# LDO_LD.net
KiCad netlist of a schematic drawn in Altium Designer
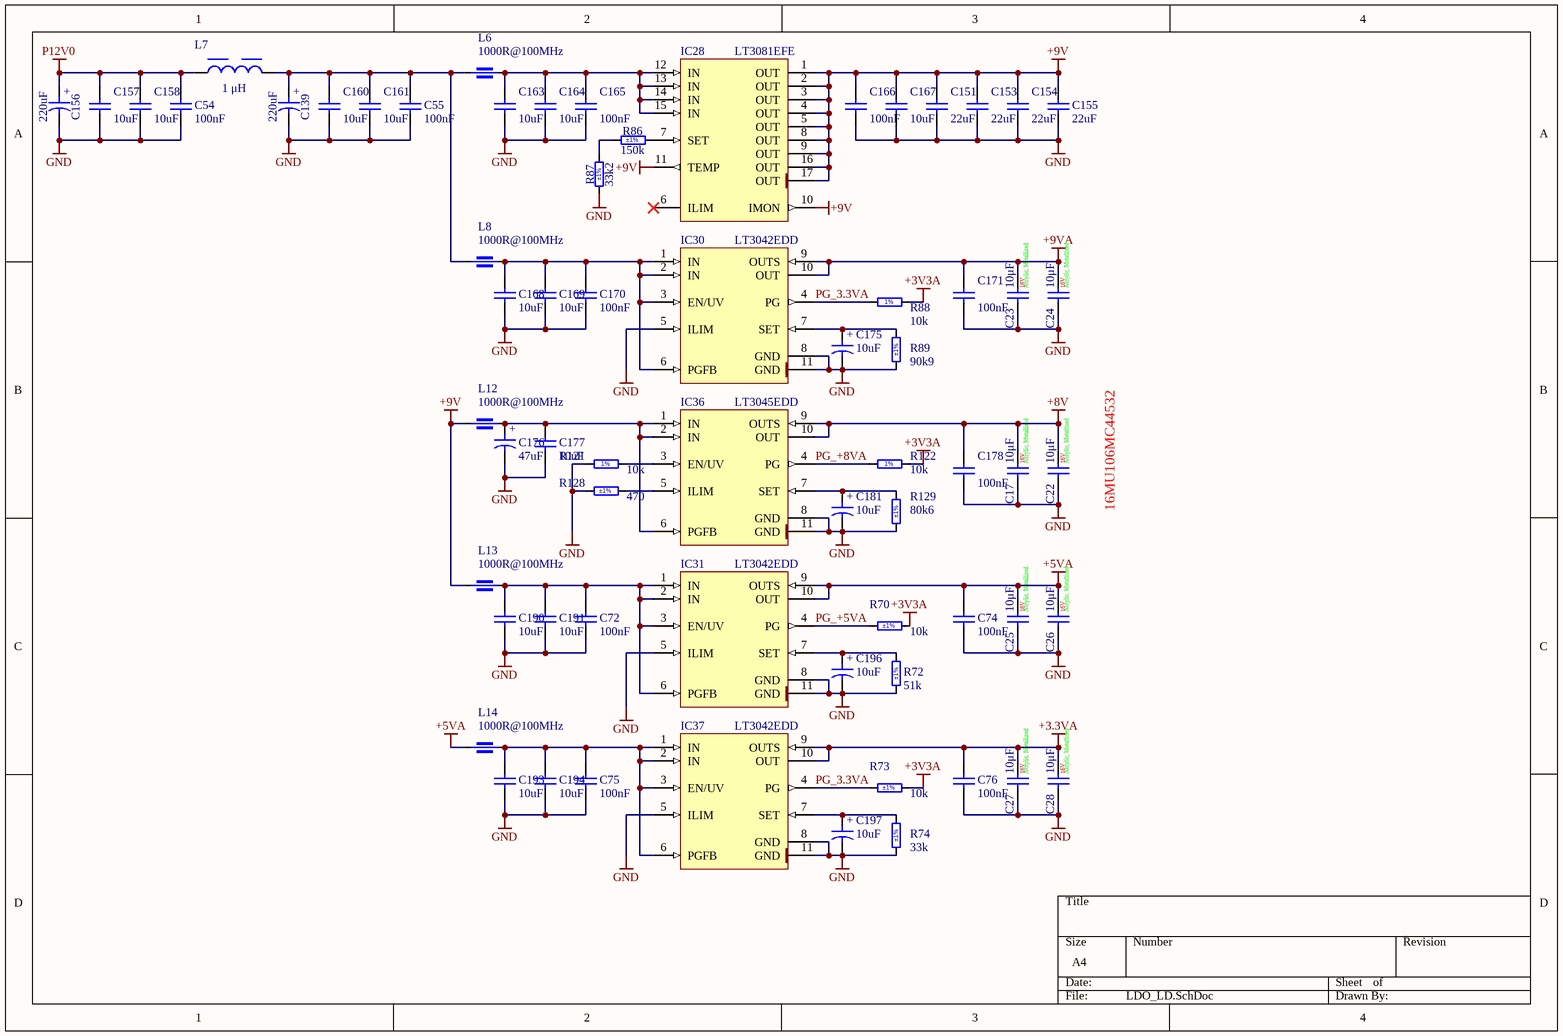
[diagram p0: LDO_LD.SchDoc]

(export (version "E")
  (design (tool "Eeschema 10.0.6"))
  (components
    (comp (ref "C17")
      (value "16MU106MC44532")
      (footprint "16MU106MC44532")
      (description "10 µF Film Capacitor 16V Acrylic, Metallized 1812 (4532 Metric)")
      (fields
        (field (name "DIELECTRIKTYPE") "Acrylic, Metallized")
        (field (name "VALUE1") "10μF")
        (field (name "VALUE2") "16V")
      )
      (libsource (lib "Component Library 3.2") (part "10uF/16V/1812/MET"))
    )
    (comp (ref "C22")
      (value "16MU106MC44532")
      (footprint "16MU106MC44532")
      (description "10 µF Film Capacitor 16V Acrylic, Metallized 1812 (4532 Metric)")
      (fields
        (field (name "DIELECTRIKTYPE") "Acrylic, Metallized")
        (field (name "VALUE1") "10μF")
        (field (name "VALUE2") "16V")
      )
      (libsource (lib "Component Library 3.2") (part "10uF/16V/1812/MET"))
    )
    (comp (ref "C23")
      (value "16MU106MC44532")
      (footprint "16MU106MC44532")
      (description "10 µF Film Capacitor 16V Acrylic, Metallized 1812 (4532 Metric)")
      (fields
        (field (name "DIELECTRIKTYPE") "Acrylic, Metallized")
        (field (name "VALUE1") "10μF")
        (field (name "VALUE2") "16V")
      )
      (libsource (lib "Component Library 3.2") (part "10uF/16V/1812/MET"))
    )
    (comp (ref "C24")
      (value "16MU106MC44532")
      (footprint "16MU106MC44532")
      (description "10 µF Film Capacitor 16V Acrylic, Metallized 1812 (4532 Metric)")
      (fields
        (field (name "DIELECTRIKTYPE") "Acrylic, Metallized")
        (field (name "VALUE1") "10μF")
        (field (name "VALUE2") "16V")
      )
      (libsource (lib "Component Library 3.2") (part "10uF/16V/1812/MET"))
    )
    (comp (ref "C25")
      (value "16MU106MC44532")
      (footprint "16MU106MC44532")
      (description "10 µF Film Capacitor 16V Acrylic, Metallized 1812 (4532 Metric)")
      (fields
        (field (name "DIELECTRIKTYPE") "Acrylic, Metallized")
        (field (name "VALUE1") "10μF")
        (field (name "VALUE2") "16V")
      )
      (libsource (lib "Component Library 3.2") (part "10uF/16V/1812/MET"))
    )
    (comp (ref "C26")
      (value "16MU106MC44532")
      (footprint "16MU106MC44532")
      (description "10 µF Film Capacitor 16V Acrylic, Metallized 1812 (4532 Metric)")
      (fields
        (field (name "DIELECTRIKTYPE") "Acrylic, Metallized")
        (field (name "VALUE1") "10μF")
        (field (name "VALUE2") "16V")
      )
      (libsource (lib "Component Library 3.2") (part "10uF/16V/1812/MET"))
    )
    (comp (ref "C27")
      (value "16MU106MC44532")
      (footprint "16MU106MC44532")
      (description "10 µF Film Capacitor 16V Acrylic, Metallized 1812 (4532 Metric)")
      (fields
        (field (name "DIELECTRIKTYPE") "Acrylic, Metallized")
        (field (name "VALUE1") "10μF")
        (field (name "VALUE2") "16V")
      )
      (libsource (lib "Component Library 3.2") (part "10uF/16V/1812/MET"))
    )
    (comp (ref "C28")
      (value "16MU106MC44532")
      (footprint "16MU106MC44532")
      (description "10 µF Film Capacitor 16V Acrylic, Metallized 1812 (4532 Metric)")
      (fields
        (field (name "DIELECTRIKTYPE") "Acrylic, Metallized")
        (field (name "VALUE1") "10μF")
        (field (name "VALUE2") "16V")
      )
      (libsource (lib "Component Library 3.2") (part "10uF/16V/1812/MET"))
    )
    (comp (ref "C54")
      (value "100nF")
      (footprint "CAPC1005X55N")
      (description "Non-polarised capacitor")
      (fields
        (field (name "PART NUMBER") "CC0402_100NF_16V_10%_X5R")
        (field (name "VOLTAGE") "16V")
        (field (name "AUTHOR") "CERN DEM JLC")
      )
      (libsource (lib "Capacitors") (part "Capacitor - non polarized"))
    )
    (comp (ref "C55")
      (value "100nF")
      (footprint "CAPC1005X55N")
      (description "Non-polarised capacitor")
      (fields
        (field (name "PART NUMBER") "CC0402_100NF_16V_10%_X5R")
        (field (name "VOLTAGE") "16V")
        (field (name "AUTHOR") "CERN DEM JLC")
      )
      (libsource (lib "Capacitors") (part "Capacitor - non polarized"))
    )
    (comp (ref "C72")
      (value "100nF")
      (footprint "CAPC1005X55N")
      (description "Non-polarised capacitor")
      (fields
        (field (name "PART NUMBER") "CC0402_100NF_16V_10%_X5R")
        (field (name "VOLTAGE") "16V")
        (field (name "AUTHOR") "CERN DEM JLC")
      )
      (libsource (lib "Capacitors") (part "Capacitor - non polarized"))
    )
    (comp (ref "C74")
      (value "100nF")
      (footprint "CAPC1005X55N")
      (description "Non-polarised capacitor")
      (fields
        (field (name "PART NUMBER") "CC0402_100NF_16V_10%_X5R")
        (field (name "VOLTAGE") "16V")
        (field (name "AUTHOR") "CERN DEM JLC")
      )
      (libsource (lib "Capacitors") (part "Capacitor - non polarized"))
    )
    (comp (ref "C75")
      (value "100nF")
      (footprint "CAPC1005X55N")
      (description "Non-polarised capacitor")
      (fields
        (field (name "PART NUMBER") "CC0402_100NF_16V_10%_X5R")
        (field (name "VOLTAGE") "16V")
        (field (name "AUTHOR") "CERN DEM JLC")
      )
      (libsource (lib "Capacitors") (part "Capacitor - non polarized"))
    )
    (comp (ref "C76")
      (value "100nF")
      (footprint "CAPC1005X55N")
      (description "Non-polarised capacitor")
      (fields
        (field (name "PART NUMBER") "CC0402_100NF_16V_10%_X5R")
        (field (name "VOLTAGE") "16V")
        (field (name "AUTHOR") "CERN DEM JLC")
      )
      (libsource (lib "Capacitors") (part "Capacitor - non polarized"))
    )
    (comp (ref "C139")
      (value "220uF")
      (footprint "CAPMP7343X430N")
      (description "Polarised capacitor")
      (fields
        (field (name "PART NUMBER") "CTE7343-43_220UF_16V_10%")
        (field (name "VOLTAGE") "16V")
        (field (name "AUTHOR") "CERN DEM JLC")
      )
      (libsource (lib "Capacitors") (part "Capacitor - polarized"))
    )
    (comp (ref "C151")
      (value "22uF")
      (footprint "CAPC3216X180N")
      (description "Non-polarised capacitor")
      (fields
        (field (name "PART NUMBER") "CC1206_22UF_10V_10%_X7R")
        (field (name "VOLTAGE") "10V")
        (field (name "AUTHOR") "CERN DEM JLC")
      )
      (libsource (lib "Capacitors") (part "Capacitor - non polarized"))
    )
    (comp (ref "C153")
      (value "22uF")
      (footprint "CAPC3216X180N")
      (description "Non-polarised capacitor")
      (fields
        (field (name "PART NUMBER") "CC1206_22UF_10V_10%_X7R")
        (field (name "VOLTAGE") "10V")
        (field (name "AUTHOR") "CERN DEM JLC")
      )
      (libsource (lib "Capacitors") (part "Capacitor - non polarized"))
    )
    (comp (ref "C154")
      (value "22uF")
      (footprint "CAPC3216X180N")
      (description "Non-polarised capacitor")
      (fields
        (field (name "PART NUMBER") "CC1206_22UF_10V_10%_X7R")
        (field (name "VOLTAGE") "10V")
        (field (name "AUTHOR") "CERN DEM JLC")
      )
      (libsource (lib "Capacitors") (part "Capacitor - non polarized"))
    )
    (comp (ref "C155")
      (value "22uF")
      (footprint "CAPC3216X180N")
      (description "Non-polarised capacitor")
      (fields
        (field (name "PART NUMBER") "CC1206_22UF_10V_10%_X7R")
        (field (name "VOLTAGE") "10V")
        (field (name "AUTHOR") "CERN DEM JLC")
      )
      (libsource (lib "Capacitors") (part "Capacitor - non polarized"))
    )
    (comp (ref "C156")
      (value "220uF")
      (footprint "CAPMP7343X430N")
      (description "Polarised capacitor")
      (fields
        (field (name "PART NUMBER") "CTE7343-43_220UF_16V_10%")
        (field (name "VOLTAGE") "16V")
        (field (name "AUTHOR") "CERN DEM JLC")
      )
      (libsource (lib "Capacitors") (part "Capacitor - polarized"))
    )
    (comp (ref "C157")
      (value "10uF")
      (footprint "CAPC2012X145N")
      (description "Non-polarised capacitor")
      (fields
        (field (name "PART NUMBER") "CC0805_10UF_25V_10%_X7R")
        (field (name "VOLTAGE") "25V")
        (field (name "AUTHOR") "CERN DEM HF")
      )
      (libsource (lib "Capacitors") (part "Capacitor - non polarized"))
    )
    (comp (ref "C158")
      (value "10uF")
      (footprint "CAPC2012X145N")
      (description "Non-polarised capacitor")
      (fields
        (field (name "PART NUMBER") "CC0805_10UF_25V_10%_X7R")
        (field (name "VOLTAGE") "25V")
        (field (name "AUTHOR") "CERN DEM HF")
      )
      (libsource (lib "Capacitors") (part "Capacitor - non polarized"))
    )
    (comp (ref "C160")
      (value "10uF")
      (footprint "CAPC2012X145N")
      (description "Non-polarised capacitor")
      (fields
        (field (name "PART NUMBER") "CC0805_10UF_25V_10%_X7R")
        (field (name "VOLTAGE") "25V")
        (field (name "AUTHOR") "CERN DEM HF")
      )
      (libsource (lib "Capacitors") (part "Capacitor - non polarized"))
    )
    (comp (ref "C161")
      (value "10uF")
      (footprint "CAPC2012X145N")
      (description "Non-polarised capacitor")
      (fields
        (field (name "PART NUMBER") "CC0805_10UF_25V_10%_X7R")
        (field (name "VOLTAGE") "25V")
        (field (name "AUTHOR") "CERN DEM HF")
      )
      (libsource (lib "Capacitors") (part "Capacitor - non polarized"))
    )
    (comp (ref "C163")
      (value "10uF")
      (footprint "CAPC2012X145N")
      (description "Non-polarised capacitor")
      (fields
        (field (name "PART NUMBER") "CC0805_10UF_25V_10%_X7R")
        (field (name "VOLTAGE") "25V")
        (field (name "AUTHOR") "CERN DEM HF")
      )
      (libsource (lib "Capacitors") (part "Capacitor - non polarized"))
    )
    (comp (ref "C164")
      (value "10uF")
      (footprint "CAPC2012X145N")
      (description "Non-polarised capacitor")
      (fields
        (field (name "PART NUMBER") "CC0805_10UF_25V_10%_X7R")
        (field (name "VOLTAGE") "25V")
        (field (name "AUTHOR") "CERN DEM HF")
      )
      (libsource (lib "Capacitors") (part "Capacitor - non polarized"))
    )
    (comp (ref "C165")
      (value "100nF")
      (footprint "CAPC1005X55N")
      (description "Non-polarised capacitor")
      (fields
        (field (name "PART NUMBER") "CC0402_100NF_16V_10%_X5R")
        (field (name "VOLTAGE") "16V")
        (field (name "AUTHOR") "CERN DEM JLC")
      )
      (libsource (lib "Capacitors") (part "Capacitor - non polarized"))
    )
    (comp (ref "C166")
      (value "100nF")
      (footprint "CAPC1005X55N")
      (description "Non-polarised capacitor")
      (fields
        (field (name "PART NUMBER") "CC0402_100NF_16V_10%_X5R")
        (field (name "VOLTAGE") "16V")
        (field (name "AUTHOR") "CERN DEM JLC")
      )
      (libsource (lib "Capacitors") (part "Capacitor - non polarized"))
    )
    (comp (ref "C167")
      (value "10uF")
      (footprint "CAPC2012X145N")
      (description "Non-polarised capacitor")
      (fields
        (field (name "PART NUMBER") "CC0805_10UF_25V_10%_X7R")
        (field (name "VOLTAGE") "25V")
        (field (name "AUTHOR") "CERN DEM HF")
      )
      (libsource (lib "Capacitors") (part "Capacitor - non polarized"))
    )
    (comp (ref "C168")
      (value "10uF")
      (footprint "CAPC2012X145N")
      (description "Non-polarised capacitor")
      (fields
        (field (name "PART NUMBER") "CC0805_10UF_25V_10%_X7R")
        (field (name "VOLTAGE") "25V")
        (field (name "AUTHOR") "CERN DEM HF")
      )
      (libsource (lib "Capacitors") (part "Capacitor - non polarized"))
    )
    (comp (ref "C169")
      (value "10uF")
      (footprint "CAPC2012X145N")
      (description "Non-polarised capacitor")
      (fields
        (field (name "PART NUMBER") "CC0805_10UF_25V_10%_X7R")
        (field (name "VOLTAGE") "25V")
        (field (name "AUTHOR") "CERN DEM HF")
      )
      (libsource (lib "Capacitors") (part "Capacitor - non polarized"))
    )
    (comp (ref "C170")
      (value "100nF")
      (footprint "CAPC1005X55N")
      (description "Non-polarised capacitor")
      (fields
        (field (name "PART NUMBER") "CC0402_100NF_16V_10%_X5R")
        (field (name "VOLTAGE") "16V")
        (field (name "AUTHOR") "CERN DEM JLC")
      )
      (libsource (lib "Capacitors") (part "Capacitor - non polarized"))
    )
    (comp (ref "C171")
      (value "100nF")
      (footprint "CAPC1005X55N")
      (description "Non-polarised capacitor")
      (fields
        (field (name "PART NUMBER") "CC0402_100NF_16V_10%_X5R")
        (field (name "VOLTAGE") "16V")
        (field (name "AUTHOR") "CERN DEM JLC")
      )
      (libsource (lib "Capacitors") (part "Capacitor - non polarized"))
    )
    (comp (ref "C175")
      (value "10uF")
      (footprint "CAPMP6032X280N")
      (description "Polarised capacitor")
      (fields
        (field (name "PART NUMBER") "CTE6032-28_10UF_25V_10%_LESR0500")
        (field (name "VOLTAGE") "25V")
        (field (name "AUTHOR") "CERN DEM JLC")
      )
      (libsource (lib "Capacitors") (part "Capacitor - polarized"))
    )
    (comp (ref "C176")
      (value "47uF")
      (footprint "CAPMP6032X280N")
      (description "Polarised capacitor")
      (fields
        (field (name "PART NUMBER") "CTE6032-28_47UF_16V_10%_LESR0350")
        (field (name "VOLTAGE") "16V")
        (field (name "AUTHOR") "CERN DEM JLC")
      )
      (libsource (lib "Capacitors") (part "Capacitor - polarized"))
    )
    (comp (ref "C177")
      (value "10uF")
      (footprint "CAPC2012X145N")
      (description "Non-polarised capacitor")
      (fields
        (field (name "PART NUMBER") "CC0805_10UF_25V_10%_X7R")
        (field (name "VOLTAGE") "25V")
        (field (name "AUTHOR") "CERN DEM HF")
      )
      (libsource (lib "Capacitors") (part "Capacitor - non polarized"))
    )
    (comp (ref "C178")
      (value "100nF")
      (footprint "CAPC1005X55N")
      (description "Non-polarised capacitor")
      (fields
        (field (name "PART NUMBER") "CC0402_100NF_16V_10%_X5R")
        (field (name "VOLTAGE") "16V")
        (field (name "AUTHOR") "CERN DEM JLC")
      )
      (libsource (lib "Capacitors") (part "Capacitor - non polarized"))
    )
    (comp (ref "C181")
      (value "10uF")
      (footprint "CAPMP6032X280N")
      (description "Polarised capacitor")
      (fields
        (field (name "PART NUMBER") "CTE6032-28_10UF_25V_10%_LESR0500")
        (field (name "VOLTAGE") "25V")
        (field (name "AUTHOR") "CERN DEM JLC")
      )
      (libsource (lib "Capacitors") (part "Capacitor - polarized"))
    )
    (comp (ref "C190")
      (value "10uF")
      (footprint "CAPC2012X145N")
      (description "Non-polarised capacitor")
      (fields
        (field (name "PART NUMBER") "CC0805_10UF_25V_10%_X7R")
        (field (name "VOLTAGE") "25V")
        (field (name "AUTHOR") "CERN DEM HF")
      )
      (libsource (lib "Capacitors") (part "Capacitor - non polarized"))
    )
    (comp (ref "C191")
      (value "10uF")
      (footprint "CAPC2012X145N")
      (description "Non-polarised capacitor")
      (fields
        (field (name "PART NUMBER") "CC0805_10UF_25V_10%_X7R")
        (field (name "VOLTAGE") "25V")
        (field (name "AUTHOR") "CERN DEM HF")
      )
      (libsource (lib "Capacitors") (part "Capacitor - non polarized"))
    )
    (comp (ref "C193")
      (value "10uF")
      (footprint "CAPC2012X145N")
      (description "Non-polarised capacitor")
      (fields
        (field (name "PART NUMBER") "CC0805_10UF_25V_10%_X7R")
        (field (name "VOLTAGE") "25V")
        (field (name "AUTHOR") "CERN DEM HF")
      )
      (libsource (lib "Capacitors") (part "Capacitor - non polarized"))
    )
    (comp (ref "C194")
      (value "10uF")
      (footprint "CAPC2012X145N")
      (description "Non-polarised capacitor")
      (fields
        (field (name "PART NUMBER") "CC0805_10UF_25V_10%_X7R")
        (field (name "VOLTAGE") "25V")
        (field (name "AUTHOR") "CERN DEM HF")
      )
      (libsource (lib "Capacitors") (part "Capacitor - non polarized"))
    )
    (comp (ref "C196")
      (value "10uF")
      (footprint "CAPMP6032X280N")
      (description "Polarised capacitor")
      (fields
        (field (name "PART NUMBER") "CTE6032-28_10UF_25V_10%_LESR0500")
        (field (name "VOLTAGE") "25V")
        (field (name "AUTHOR") "CERN DEM JLC")
      )
      (libsource (lib "Capacitors") (part "Capacitor - polarized"))
    )
    (comp (ref "C197")
      (value "10uF")
      (footprint "CAPMP6032X280N")
      (description "Polarised capacitor")
      (fields
        (field (name "PART NUMBER") "CTE6032-28_10UF_25V_10%_LESR0500")
        (field (name "VOLTAGE") "25V")
        (field (name "AUTHOR") "CERN DEM JLC")
      )
      (libsource (lib "Capacitors") (part "Capacitor - polarized"))
    )
    (comp (ref "IC28")
      (value "LT3081EFE")
      (footprint "SOP65P640X110-17N-R294X358")
      (description "1.2 To 36V, 1.5A Single Resistor Rugged Linear Regulator With Monitors")
      (fields
        (field (name "PART NUMBER") "LT3081EFE#PBF")
        (field (name "MANUFACTURER") "LINEAR TECHNOLOGY")
        (field (name "AUTHOR") "CERN DEM MR")
      )
      (libsource (lib "ICs And Semiconductors") (part "LT3081EFE"))
    )
    (comp (ref "IC30")
      (value "LT3042EDD")
      (footprint "SON50P300X300X80-11N-R175X248")
      (description "20V, 200mA, Ultralow Noise, Ultrahigh PSRR RF Linear Regulator")
      (fields (field (name "MANUFACTURER") "ANALOG DEVICES") (field (name "AUTHOR") "CERN DEM HF"))
      (libsource (lib "ICs And Semiconductors") (part "LT3042"))
    )
    (comp (ref "IC31")
      (value "LT3042EDD")
      (footprint "SON50P300X300X80-11N-R175X248")
      (description "20V, 200mA, Ultralow Noise, Ultrahigh PSRR RF Linear Regulator")
      (fields (field (name "MANUFACTURER") "ANALOG DEVICES") (field (name "AUTHOR") "CERN DEM HF"))
      (libsource (lib "ICs And Semiconductors") (part "LT3042"))
    )
    (comp (ref "IC36")
      (value "LT3045EDD")
      (footprint "SON50P300X300X80-11N-R175X248")
      (description "20V, 500mA, Ultralow Noise, Ultrahigh PSRR Linear Regulator")
      (fields
        (field (name "PART NUMBER") "LT3045EDD#PBF")
        (field (name "MANUFACTURER") "LINEAR TECHNOLOGY")
        (field (name "AUTHOR") "CERN DEM JLC")
      )
      (libsource (lib "ICs And Semiconductors") (part "LT3045EDD"))
    )
    (comp (ref "IC37")
      (value "LT3042EDD")
      (footprint "SON50P300X300X80-11N-R175X248")
      (description "20V, 200mA, Ultralow Noise, Ultrahigh PSRR RF Linear Regulator")
      (fields (field (name "MANUFACTURER") "ANALOG DEVICES") (field (name "AUTHOR") "CERN DEM HF"))
      (libsource (lib "ICs And Semiconductors") (part "LT3042"))
    )
    (comp (ref "L6")
      (value "1000R@100MHz")
      (footprint "INDC1608X95N")
      (fields
        (field (name "PART NUMBER") "IND0603_MURATA_BLM18KG102SN1")
        (field (name "POWER") "1A")
        (field (name "TOLERANCE") "±25%")
        (field (name "AUTHOR") "CERN DEM HF")
      )
      (libsource (lib "Inductors & Transformers") (part "Ferrite Bead"))
    )
    (comp (ref "L7")
      (value "1 μH")
      (footprint "WE-MAPI_2510")
      (description "WE-MAPI SMT Power Inductor, size 2510, 1 μH, 3.55 A, 63 mΩ")
      (fields
        (field (name "MANUFACTURER PART NUMBER") "74438323010")
        (field (name "MANUFACTURER") "Wurth Elektronik")
      )
      (libsource (lib "WE-MAPI (rev25a)") (part "74438323010"))
    )
    (comp (ref "L8")
      (value "1000R@100MHz")
      (footprint "INDC1608X95N")
      (fields
        (field (name "PART NUMBER") "IND0603_MURATA_BLM18KG102SN1")
        (field (name "POWER") "1A")
        (field (name "TOLERANCE") "±25%")
        (field (name "AUTHOR") "CERN DEM HF")
      )
      (libsource (lib "Inductors & Transformers") (part "Ferrite Bead"))
    )
    (comp (ref "L12")
      (value "1000R@100MHz")
      (footprint "INDC1608X95N")
      (fields
        (field (name "PART NUMBER") "IND0603_MURATA_BLM18KG102SN1")
        (field (name "POWER") "1A")
        (field (name "TOLERANCE") "±25%")
        (field (name "AUTHOR") "CERN DEM HF")
      )
      (libsource (lib "Inductors & Transformers") (part "Ferrite Bead"))
    )
    (comp (ref "L13")
      (value "1000R@100MHz")
      (footprint "INDC1608X95N")
      (fields
        (field (name "PART NUMBER") "IND0603_MURATA_BLM18KG102SN1")
        (field (name "POWER") "1A")
        (field (name "TOLERANCE") "±25%")
        (field (name "AUTHOR") "CERN DEM HF")
      )
      (libsource (lib "Inductors & Transformers") (part "Ferrite Bead"))
    )
    (comp (ref "L14")
      (value "1000R@100MHz")
      (footprint "INDC1608X95N")
      (fields
        (field (name "PART NUMBER") "IND0603_MURATA_BLM18KG102SN1")
        (field (name "POWER") "1A")
        (field (name "TOLERANCE") "±25%")
        (field (name "AUTHOR") "CERN DEM HF")
      )
      (libsource (lib "Inductors & Transformers") (part "Ferrite Bead"))
    )
    (comp (ref "R70")
      (value "10k")
      (footprint "RESC1005X40N")
      (description "Resistor - 1%")
      (fields
        (field (name "TOLERANCE") "±1%")
        (field (name "PART NUMBER") "R0402_10K_1%_0.0625W_100PPM")
        (field (name "POWER") "0.0625W")
        (field (name "AUTHOR") "CERN DEM JLC")
      )
      (libsource (lib "Resistors") (part "Resistor - 1%"))
    )
    (comp (ref "R72")
      (value "51k")
      (footprint "RESC1005X40N")
      (description "Resistor - 1%")
      (fields
        (field (name "TOLERANCE") "±1%")
        (field (name "PART NUMBER") "R0402_51K_1%_0.0625W_100PPM")
        (field (name "POWER") "0.0625W")
        (field (name "AUTHOR") "CERN DEM JLC")
      )
      (libsource (lib "Resistors") (part "Resistor - 1%"))
    )
    (comp (ref "R73")
      (value "10k")
      (footprint "RESC1005X40N")
      (description "Resistor - 1%")
      (fields
        (field (name "TOLERANCE") "±1%")
        (field (name "PART NUMBER") "R0402_10K_1%_0.0625W_100PPM")
        (field (name "POWER") "0.0625W")
        (field (name "AUTHOR") "CERN DEM JLC")
      )
      (libsource (lib "Resistors") (part "Resistor - 1%"))
    )
    (comp (ref "R74")
      (value "33k")
      (footprint "RESC1005X40N")
      (description "Resistor - 1%")
      (fields
        (field (name "TOLERANCE") "±1%")
        (field (name "PART NUMBER") "R0402_33K_1%_0.0625W_100PPM")
        (field (name "POWER") "0.0625W")
        (field (name "AUTHOR") "CERN DEM JLC")
      )
      (libsource (lib "Resistors") (part "Resistor - 1%"))
    )
    (comp (ref "R86")
      (value "150k")
      (footprint "RESC1608X55N")
      (description "Resistor - 1%")
      (fields
        (field (name "TOLERANCE") "±1%")
        (field (name "PART NUMBER") "R0603_150K_1%_0.1W_100PPM")
        (field (name "POWER") "0.1W")
        (field (name "AUTHOR") "CERN DEM JLC")
      )
      (libsource (lib "Resistors") (part "Resistor - 1%"))
    )
    (comp (ref "R87")
      (value "33k2")
      (footprint "RESC1608X55N")
      (description "Resistor - 1%")
      (fields
        (field (name "TOLERANCE") "±1%")
        (field (name "PART NUMBER") "R0603_33K2_1%_0.1W_100PPM")
        (field (name "POWER") "0.1W")
        (field (name "AUTHOR") "CERN DEM JLC")
      )
      (libsource (lib "Resistors") (part "Resistor - 1%"))
    )
    (comp (ref "R88")
      (value "10k")
      (footprint "RESC1005X40N")
      (description "Resistor - 1%")
      (fields
        (field (name "PART NUMBER") "R0402_10K_1%_0.0625W_100PPM")
        (field (name "POWER") "0.0625W")
        (field (name "AUTHOR") "CERN DEM JLC")
      )
      (libsource (lib "Resistors") (part "Resistor - 1%"))
    )
    (comp (ref "R89")
      (value "90k9")
      (footprint "RESC1608X55N")
      (description "Resistor - 1%")
      (fields
        (field (name "TOLERANCE") "±1%")
        (field (name "PART NUMBER") "R0603_90K9_1%_0.1W_100PPM")
        (field (name "POWER") "0.1W")
        (field (name "AUTHOR") "CERN DEM JLC")
      )
      (libsource (lib "Resistors") (part "Resistor - 1%"))
    )
    (comp (ref "R121")
      (value "10k")
      (footprint "RESC1005X40N")
      (description "Resistor - 1%")
      (fields
        (field (name "PART NUMBER") "R0402_10K_1%_0.0625W_100PPM")
        (field (name "POWER") "0.0625W")
        (field (name "AUTHOR") "CERN DEM JLC")
      )
      (libsource (lib "Resistors") (part "Resistor - 1%"))
    )
    (comp (ref "R122")
      (value "10k")
      (footprint "RESC1005X40N")
      (description "Resistor - 1%")
      (fields
        (field (name "PART NUMBER") "R0402_10K_1%_0.0625W_100PPM")
        (field (name "POWER") "0.0625W")
        (field (name "AUTHOR") "CERN DEM JLC")
      )
      (libsource (lib "Resistors") (part "Resistor - 1%"))
    )
    (comp (ref "R128")
      (value "470")
      (footprint "RESC1608X55N")
      (description "Resistor - 1%")
      (fields
        (field (name "TOLERANCE") "±1%")
        (field (name "PART NUMBER") "R0603_470R_1%_0.1W_100PPM")
        (field (name "POWER") "0.1W")
        (field (name "AUTHOR") "CERN DEM JLC")
      )
      (libsource (lib "Resistors") (part "Resistor - 1%"))
    )
    (comp (ref "R129")
      (value "80k6")
      (footprint "RESC1608X55N")
      (description "Resistor - 1%")
      (fields
        (field (name "TOLERANCE") "±1%")
        (field (name "PART NUMBER") "R0603_80k6_1%_0.1W_100PPM_BOURNS_CR0603")
        (field (name "POWER") "0.1W")
        (field (name "AUTHOR") "CERN DEM HF")
      )
      (libsource (lib "Resistors") (part "Resistor - 1%"))
    )
  )
  (nets
    (net (code "1") (name "+3.3VA") (class "Default")
      (node (ref "C27") (pin "2") (pinfunction "2_2") (pintype "passive"))
      (node (ref "C28") (pin "2") (pinfunction "2_2") (pintype "passive"))
      (node (ref "C76") (pin "1") (pinfunction "1_1") (pintype "passive"))
      (node (ref "IC37") (pin "10") (pinfunction "OUT_10") (pintype "power_in"))
      (node (ref "IC37") (pin "9") (pinfunction "OUTS_9") (pintype "input"))
    )
    (net (code "2") (name "+3V3A") (class "Default")
      (node (ref "R122") (pin "2") (pinfunction "2_2") (pintype "passive"))
      (node (ref "R70") (pin "2") (pinfunction "2_2") (pintype "passive"))
      (node (ref "R73") (pin "2") (pinfunction "2_2") (pintype "passive"))
      (node (ref "R88") (pin "2") (pinfunction "2_2") (pintype "passive"))
    )
    (net (code "3") (name "+5VA") (class "Default")
      (node (ref "C25") (pin "2") (pinfunction "2_2") (pintype "passive"))
      (node (ref "C26") (pin "2") (pinfunction "2_2") (pintype "passive"))
      (node (ref "C74") (pin "1") (pinfunction "1_1") (pintype "passive"))
      (node (ref "IC31") (pin "10") (pinfunction "OUT_10") (pintype "power_in"))
      (node (ref "IC31") (pin "9") (pinfunction "OUTS_9") (pintype "input"))
      (node (ref "L14") (pin "1") (pinfunction "1_1") (pintype "passive"))
    )
    (net (code "4") (name "+8V") (class "Default")
      (node (ref "C17") (pin "2") (pinfunction "2_2") (pintype "passive"))
      (node (ref "C178") (pin "1") (pinfunction "1_1") (pintype "passive"))
      (node (ref "C22") (pin "2") (pinfunction "2_2") (pintype "passive"))
      (node (ref "IC36") (pin "10") (pinfunction "OUT_10") (pintype "power_in"))
      (node (ref "IC36") (pin "9") (pinfunction "OUTS_9") (pintype "input"))
    )
    (net (code "5") (name "+9V") (class "Default")
      (node (ref "C151") (pin "2") (pinfunction "2_2") (pintype "passive"))
      (node (ref "C153") (pin "2") (pinfunction "2_2") (pintype "passive"))
      (node (ref "C154") (pin "2") (pinfunction "2_2") (pintype "passive"))
      (node (ref "C155") (pin "2") (pinfunction "2_2") (pintype "passive"))
      (node (ref "C166") (pin "1") (pinfunction "1_1") (pintype "passive"))
      (node (ref "C167") (pin "2") (pinfunction "2_2") (pintype "passive"))
      (node (ref "IC28") (pin "1") (pinfunction "OUT_1") (pintype "power_in"))
      (node (ref "IC28") (pin "10") (pinfunction "IMON_10") (pintype "output"))
      (node (ref "IC28") (pin "11") (pinfunction "TEMP_11") (pintype "output"))
      (node (ref "IC28") (pin "16") (pinfunction "OUT_16") (pintype "power_in"))
      (node (ref "IC28") (pin "17") (pinfunction "OUT_17") (pintype "power_in"))
      (node (ref "IC28") (pin "2") (pinfunction "OUT_2") (pintype "power_in"))
      (node (ref "IC28") (pin "3") (pinfunction "OUT_3") (pintype "power_in"))
      (node (ref "IC28") (pin "4") (pinfunction "OUT_4") (pintype "power_in"))
      (node (ref "IC28") (pin "5") (pinfunction "OUT_5") (pintype "power_in"))
      (node (ref "IC28") (pin "8") (pinfunction "OUT_8") (pintype "power_in"))
      (node (ref "IC28") (pin "9") (pinfunction "OUT_9") (pintype "power_in"))
      (node (ref "L12") (pin "1") (pinfunction "1_1") (pintype "passive"))
      (node (ref "L13") (pin "1") (pinfunction "1_1") (pintype "passive"))
    )
    (net (code "6") (name "+9VA") (class "Default")
      (node (ref "C171") (pin "1") (pinfunction "1_1") (pintype "passive"))
      (node (ref "C23") (pin "2") (pinfunction "2_2") (pintype "passive"))
      (node (ref "C24") (pin "2") (pinfunction "2_2") (pintype "passive"))
      (node (ref "IC30") (pin "10") (pinfunction "OUT_10") (pintype "power_in"))
      (node (ref "IC30") (pin "9") (pinfunction "OUTS_9") (pintype "input"))
    )
    (net (code "7") (name "/PG_+5VA") (class "Default")
      (node (ref "IC31") (pin "4") (pinfunction "PG_4") (pintype "output"))
      (node (ref "R70") (pin "1") (pinfunction "1_1") (pintype "passive"))
    )
    (net (code "8") (name "/PG_+8VA") (class "Default")
      (node (ref "IC36") (pin "4") (pinfunction "PG_4") (pintype "output"))
      (node (ref "R122") (pin "1") (pinfunction "1_1") (pintype "passive"))
    )
    (net (code "9") (name "/PG_3.3VA") (class "Default")
      (node (ref "IC30") (pin "4") (pinfunction "PG_4") (pintype "output"))
      (node (ref "IC37") (pin "4") (pinfunction "PG_4") (pintype "output"))
      (node (ref "R73") (pin "1") (pinfunction "1_1") (pintype "passive"))
      (node (ref "R88") (pin "1") (pinfunction "1_1") (pintype "passive"))
    )
    (net (code "10") (name "GND") (class "Default")
      (node (ref "C139") (pin "2") (pinfunction "2_2") (pintype "passive"))
      (node (ref "C151") (pin "1") (pinfunction "1_1") (pintype "passive"))
      (node (ref "C153") (pin "1") (pinfunction "1_1") (pintype "passive"))
      (node (ref "C154") (pin "1") (pinfunction "1_1") (pintype "passive"))
      (node (ref "C155") (pin "1") (pinfunction "1_1") (pintype "passive"))
      (node (ref "C156") (pin "2") (pinfunction "2_2") (pintype "passive"))
      (node (ref "C157") (pin "1") (pinfunction "1_1") (pintype "passive"))
      (node (ref "C158") (pin "1") (pinfunction "1_1") (pintype "passive"))
      (node (ref "C160") (pin "1") (pinfunction "1_1") (pintype "passive"))
      (node (ref "C161") (pin "1") (pinfunction "1_1") (pintype "passive"))
      (node (ref "C163") (pin "1") (pinfunction "1_1") (pintype "passive"))
      (node (ref "C164") (pin "1") (pinfunction "1_1") (pintype "passive"))
      (node (ref "C165") (pin "2") (pinfunction "2_2") (pintype "passive"))
      (node (ref "C166") (pin "2") (pinfunction "2_2") (pintype "passive"))
      (node (ref "C167") (pin "1") (pinfunction "1_1") (pintype "passive"))
      (node (ref "C168") (pin "1") (pinfunction "1_1") (pintype "passive"))
      (node (ref "C169") (pin "1") (pinfunction "1_1") (pintype "passive"))
      (node (ref "C17") (pin "1") (pinfunction "1_1") (pintype "passive"))
      (node (ref "C170") (pin "2") (pinfunction "2_2") (pintype "passive"))
      (node (ref "C171") (pin "2") (pinfunction "2_2") (pintype "passive"))
      (node (ref "C175") (pin "2") (pinfunction "2_2") (pintype "passive"))
      (node (ref "C176") (pin "2") (pinfunction "2_2") (pintype "passive"))
      (node (ref "C177") (pin "1") (pinfunction "1_1") (pintype "passive"))
      (node (ref "C178") (pin "2") (pinfunction "2_2") (pintype "passive"))
      (node (ref "C181") (pin "2") (pinfunction "2_2") (pintype "passive"))
      (node (ref "C190") (pin "1") (pinfunction "1_1") (pintype "passive"))
      (node (ref "C191") (pin "1") (pinfunction "1_1") (pintype "passive"))
      (node (ref "C193") (pin "1") (pinfunction "1_1") (pintype "passive"))
      (node (ref "C194") (pin "1") (pinfunction "1_1") (pintype "passive"))
      (node (ref "C196") (pin "2") (pinfunction "2_2") (pintype "passive"))
      (node (ref "C197") (pin "2") (pinfunction "2_2") (pintype "passive"))
      (node (ref "C22") (pin "1") (pinfunction "1_1") (pintype "passive"))
      (node (ref "C23") (pin "1") (pinfunction "1_1") (pintype "passive"))
      (node (ref "C24") (pin "1") (pinfunction "1_1") (pintype "passive"))
      (node (ref "C25") (pin "1") (pinfunction "1_1") (pintype "passive"))
      (node (ref "C26") (pin "1") (pinfunction "1_1") (pintype "passive"))
      (node (ref "C27") (pin "1") (pinfunction "1_1") (pintype "passive"))
      (node (ref "C28") (pin "1") (pinfunction "1_1") (pintype "passive"))
      (node (ref "C54") (pin "2") (pinfunction "2_2") (pintype "passive"))
      (node (ref "C55") (pin "2") (pinfunction "2_2") (pintype "passive"))
      (node (ref "C72") (pin "2") (pinfunction "2_2") (pintype "passive"))
      (node (ref "C74") (pin "2") (pinfunction "2_2") (pintype "passive"))
      (node (ref "C75") (pin "2") (pinfunction "2_2") (pintype "passive"))
      (node (ref "C76") (pin "2") (pinfunction "2_2") (pintype "passive"))
      (node (ref "IC30") (pin "11") (pinfunction "GND_11") (pintype "power_in"))
      (node (ref "IC30") (pin "5") (pinfunction "ILIM_5") (pintype "input"))
      (node (ref "IC30") (pin "8") (pinfunction "GND_8") (pintype "power_in"))
      (node (ref "IC31") (pin "11") (pinfunction "GND_11") (pintype "power_in"))
      (node (ref "IC31") (pin "5") (pinfunction "ILIM_5") (pintype "input"))
      (node (ref "IC31") (pin "8") (pinfunction "GND_8") (pintype "power_in"))
      (node (ref "IC36") (pin "11") (pinfunction "GND_11") (pintype "power_in"))
      (node (ref "IC36") (pin "8") (pinfunction "GND_8") (pintype "power_in"))
      (node (ref "IC37") (pin "11") (pinfunction "GND_11") (pintype "power_in"))
      (node (ref "IC37") (pin "5") (pinfunction "ILIM_5") (pintype "input"))
      (node (ref "IC37") (pin "8") (pinfunction "GND_8") (pintype "power_in"))
      (node (ref "R121") (pin "1") (pinfunction "1_1") (pintype "passive"))
      (node (ref "R128") (pin "1") (pinfunction "1_1") (pintype "passive"))
      (node (ref "R129") (pin "1") (pinfunction "1_1") (pintype "passive"))
      (node (ref "R72") (pin "1") (pinfunction "1_1") (pintype "passive"))
      (node (ref "R74") (pin "1") (pinfunction "1_1") (pintype "passive"))
      (node (ref "R87") (pin "1") (pinfunction "1_1") (pintype "passive"))
      (node (ref "R89") (pin "1") (pinfunction "1_1") (pintype "passive"))
    )
    (net (code "11") (name "Net-(C139-Pad1)") (class "Default")
      (node (ref "C139") (pin "1") (pinfunction "1_1") (pintype "passive"))
      (node (ref "C160") (pin "2") (pinfunction "2_2") (pintype "passive"))
      (node (ref "C161") (pin "2") (pinfunction "2_2") (pintype "passive"))
      (node (ref "C55") (pin "1") (pinfunction "1_1") (pintype "passive"))
      (node (ref "L6") (pin "1") (pinfunction "1_1") (pintype "passive"))
      (node (ref "L7") (pin "2") (pinfunction "2_2") (pintype "passive"))
      (node (ref "L8") (pin "1") (pinfunction "1_1") (pintype "passive"))
    )
    (net (code "12") (name "Net-(C163-Pad2)") (class "Default")
      (node (ref "C163") (pin "2") (pinfunction "2_2") (pintype "passive"))
      (node (ref "C164") (pin "2") (pinfunction "2_2") (pintype "passive"))
      (node (ref "C165") (pin "1") (pinfunction "1_1") (pintype "passive"))
      (node (ref "IC28") (pin "12") (pinfunction "IN_12") (pintype "input"))
      (node (ref "IC28") (pin "13") (pinfunction "IN_13") (pintype "input"))
      (node (ref "IC28") (pin "14") (pinfunction "IN_14") (pintype "input"))
      (node (ref "IC28") (pin "15") (pinfunction "IN_15") (pintype "input"))
      (node (ref "L6") (pin "2") (pinfunction "2_2") (pintype "passive"))
    )
    (net (code "13") (name "Net-(IC28-SET)") (class "Default")
      (node (ref "IC28") (pin "7") (pinfunction "SET_7") (pintype "input"))
      (node (ref "R86") (pin "2") (pinfunction "2_2") (pintype "passive"))
    )
    (net (code "14") (name "Net-(IC30-EN{slash}UV)") (class "Default")
      (node (ref "C168") (pin "2") (pinfunction "2_2") (pintype "passive"))
      (node (ref "C169") (pin "2") (pinfunction "2_2") (pintype "passive"))
      (node (ref "C170") (pin "1") (pinfunction "1_1") (pintype "passive"))
      (node (ref "IC30") (pin "1") (pinfunction "IN_1") (pintype "input"))
      (node (ref "IC30") (pin "2") (pinfunction "IN_2") (pintype "input"))
      (node (ref "IC30") (pin "3") (pinfunction "EN/UV_3") (pintype "input"))
      (node (ref "IC30") (pin "6") (pinfunction "PGFB_6") (pintype "input"))
      (node (ref "L8") (pin "2") (pinfunction "2_2") (pintype "passive"))
    )
    (net (code "15") (name "Net-(IC30-SET)") (class "Default")
      (node (ref "C175") (pin "1") (pinfunction "1_1") (pintype "passive"))
      (node (ref "IC30") (pin "7") (pinfunction "SET_7") (pintype "input"))
      (node (ref "R89") (pin "2") (pinfunction "2_2") (pintype "passive"))
    )
    (net (code "16") (name "Net-(IC31-EN{slash}UV)") (class "Default")
      (node (ref "C190") (pin "2") (pinfunction "2_2") (pintype "passive"))
      (node (ref "C191") (pin "2") (pinfunction "2_2") (pintype "passive"))
      (node (ref "C72") (pin "1") (pinfunction "1_1") (pintype "passive"))
      (node (ref "IC31") (pin "1") (pinfunction "IN_1") (pintype "input"))
      (node (ref "IC31") (pin "2") (pinfunction "IN_2") (pintype "input"))
      (node (ref "IC31") (pin "3") (pinfunction "EN/UV_3") (pintype "input"))
      (node (ref "IC31") (pin "6") (pinfunction "PGFB_6") (pintype "input"))
      (node (ref "L13") (pin "2") (pinfunction "2_2") (pintype "passive"))
    )
    (net (code "17") (name "Net-(IC31-SET)") (class "Default")
      (node (ref "C196") (pin "1") (pinfunction "1_1") (pintype "passive"))
      (node (ref "IC31") (pin "7") (pinfunction "SET_7") (pintype "input"))
      (node (ref "R72") (pin "2") (pinfunction "2_2") (pintype "passive"))
    )
    (net (code "18") (name "Net-(IC36-EN{slash}UV)") (class "Default")
      (node (ref "IC36") (pin "3") (pinfunction "EN/UV_3") (pintype "input"))
      (node (ref "R121") (pin "2") (pinfunction "2_2") (pintype "passive"))
    )
    (net (code "19") (name "Net-(IC36-ILIM)") (class "Default")
      (node (ref "IC36") (pin "5") (pinfunction "ILIM_5") (pintype "input"))
      (node (ref "R128") (pin "2") (pinfunction "2_2") (pintype "passive"))
    )
    (net (code "20") (name "Net-(IC36-PGFB)") (class "Default")
      (node (ref "C176") (pin "1") (pinfunction "1_1") (pintype "passive"))
      (node (ref "C177") (pin "2") (pinfunction "2_2") (pintype "passive"))
      (node (ref "IC36") (pin "1") (pinfunction "IN_1") (pintype "input"))
      (node (ref "IC36") (pin "2") (pinfunction "IN_2") (pintype "input"))
      (node (ref "IC36") (pin "6") (pinfunction "PGFB_6") (pintype "input"))
      (node (ref "L12") (pin "2") (pinfunction "2_2") (pintype "passive"))
    )
    (net (code "21") (name "Net-(IC36-SET)") (class "Default")
      (node (ref "C181") (pin "1") (pinfunction "1_1") (pintype "passive"))
      (node (ref "IC36") (pin "7") (pinfunction "SET_7") (pintype "input"))
      (node (ref "R129") (pin "2") (pinfunction "2_2") (pintype "passive"))
    )
    (net (code "22") (name "Net-(IC37-EN{slash}UV)") (class "Default")
      (node (ref "C193") (pin "2") (pinfunction "2_2") (pintype "passive"))
      (node (ref "C194") (pin "2") (pinfunction "2_2") (pintype "passive"))
      (node (ref "C75") (pin "1") (pinfunction "1_1") (pintype "passive"))
      (node (ref "IC37") (pin "1") (pinfunction "IN_1") (pintype "input"))
      (node (ref "IC37") (pin "2") (pinfunction "IN_2") (pintype "input"))
      (node (ref "IC37") (pin "3") (pinfunction "EN/UV_3") (pintype "input"))
      (node (ref "IC37") (pin "6") (pinfunction "PGFB_6") (pintype "input"))
      (node (ref "L14") (pin "2") (pinfunction "2_2") (pintype "passive"))
    )
    (net (code "23") (name "Net-(IC37-SET)") (class "Default")
      (node (ref "C197") (pin "1") (pinfunction "1_1") (pintype "passive"))
      (node (ref "IC37") (pin "7") (pinfunction "SET_7") (pintype "input"))
      (node (ref "R74") (pin "2") (pinfunction "2_2") (pintype "passive"))
    )
    (net (code "24") (name "Net-(R86-Pad1)") (class "Default")
      (node (ref "R86") (pin "1") (pinfunction "1_1") (pintype "passive"))
      (node (ref "R87") (pin "2") (pinfunction "2_2") (pintype "passive"))
    )
    (net (code "25") (name "P12V0") (class "Default")
      (node (ref "C156") (pin "1") (pinfunction "1_1") (pintype "passive"))
      (node (ref "C157") (pin "2") (pinfunction "2_2") (pintype "passive"))
      (node (ref "C158") (pin "2") (pinfunction "2_2") (pintype "passive"))
      (node (ref "C54") (pin "1") (pinfunction "1_1") (pintype "passive"))
      (node (ref "L7") (pin "1") (pinfunction "1_1") (pintype "passive"))
    )
    (net (code "26") (name "unconnected-(IC28-ILIM-Pad6)") (class "Default")
      (node (ref "IC28") (pin "6") (pinfunction "ILIM_6") (pintype "passive+no_connect"))
    )
  )
)
